# alte_schaltung.net
KiCad netlist of a schematic drawn in EAGLE
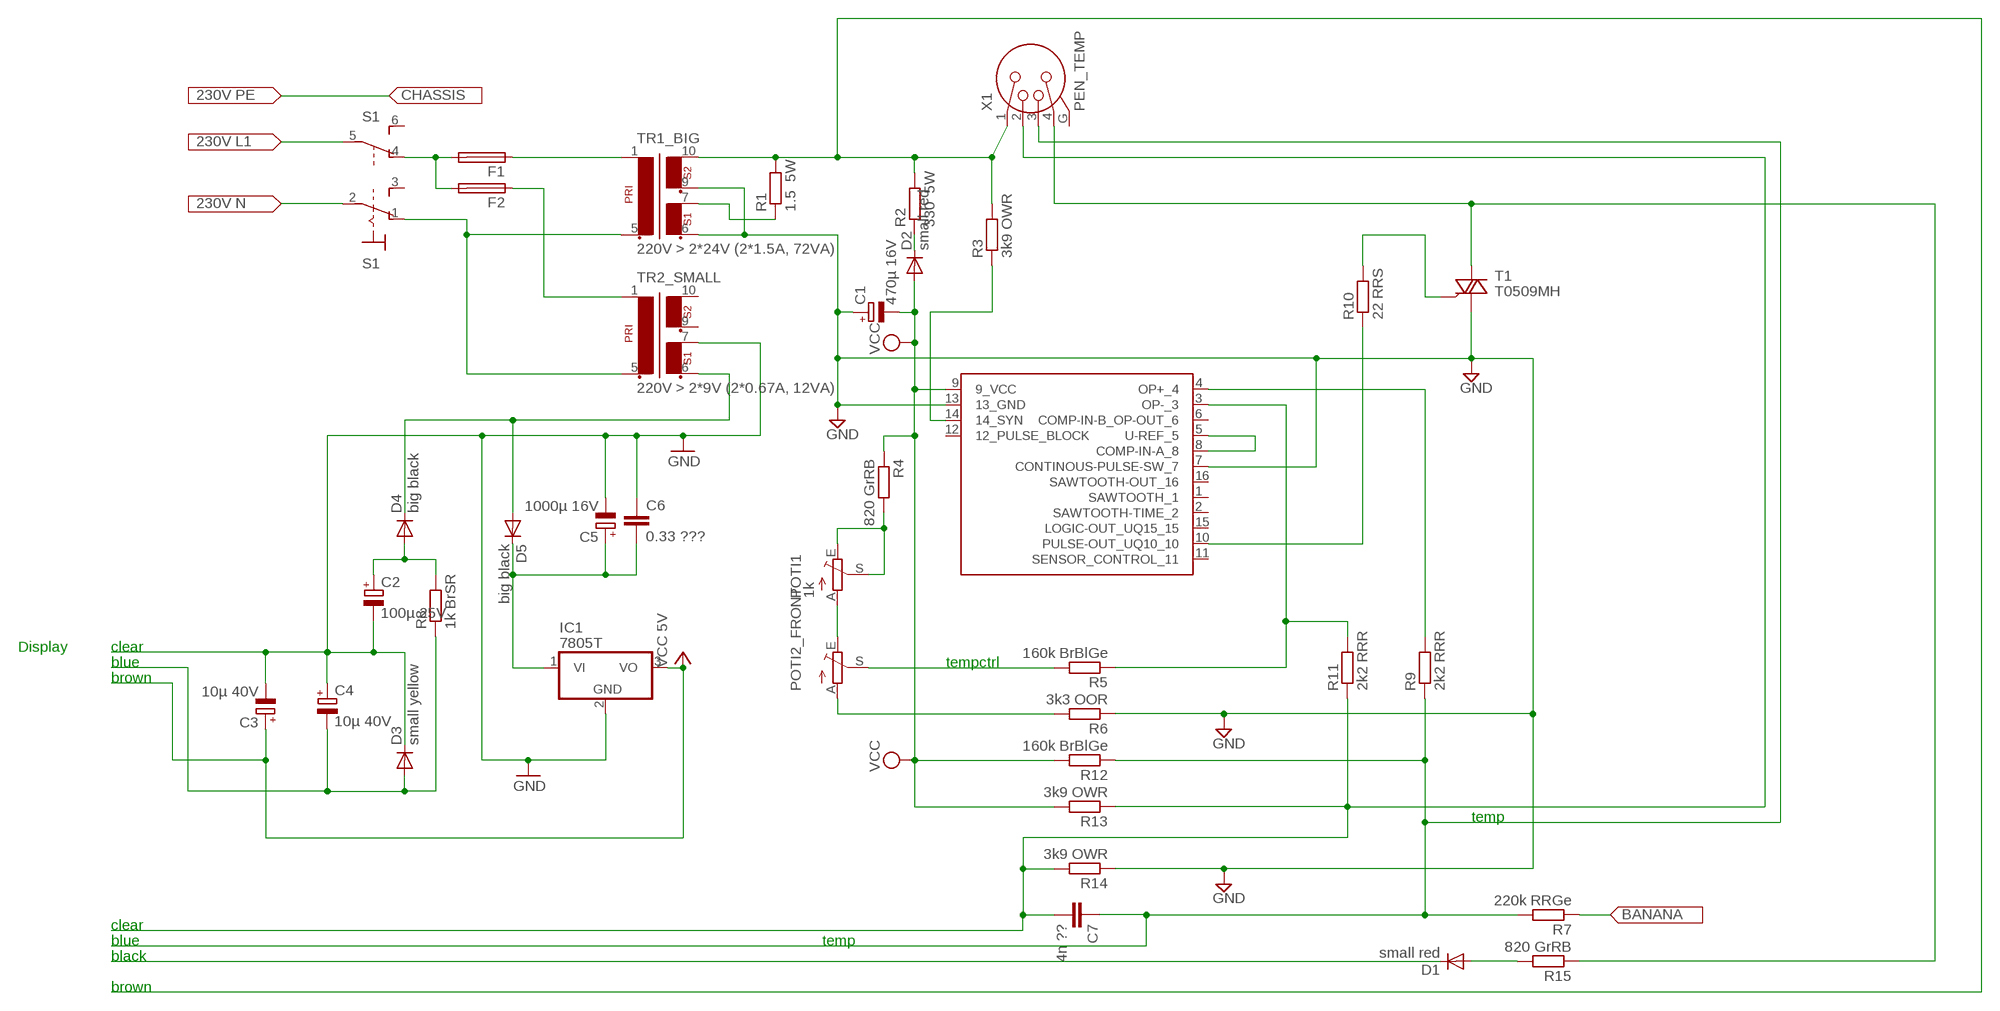
[diagram p0: schematic, sheet 1]

(export (version "E")
  (design (tool "Eeschema 10.0.6"))
  (components
    (comp (ref "C1")
      (value "470µ 16V")
      (footprint "eagle-import:E5-10,5")
      (libsource (lib "eagle-import") (part "CPOL-EUE5-10.5"))
    )
    (comp (ref "C2")
      (value "100µ 25V")
      (footprint "eagle-import:E5-10,5")
      (libsource (lib "eagle-import") (part "CPOL-EUE5-10.5"))
    )
    (comp (ref "C3")
      (value "10µ 40V")
      (footprint "eagle-import:E5-10,5")
      (libsource (lib "eagle-import") (part "CPOL-EUE5-10.5"))
    )
    (comp (ref "C4")
      (value "10µ 40V")
      (footprint "eagle-import:E5-10,5")
      (libsource (lib "eagle-import") (part "CPOL-EUE5-10.5"))
    )
    (comp (ref "C5")
      (value "1000µ 16V")
      (footprint "eagle-import:E5-10,5")
      (libsource (lib "eagle-import") (part "CPOL-EUE5-10.5"))
    )
    (comp (ref "C6")
      (value "0.33 ???")
      (footprint "eagle-import:C075-042X103")
      (libsource (lib "eagle-import") (part "C-EU075-042X103"))
    )
    (comp (ref "C7")
      (value "4n ??")
      (footprint "eagle-import:C050-024X044")
      (libsource (lib "eagle-import") (part "C-EU050-024X044"))
    )
    (comp (ref "D1")
      (value "small red")
      (footprint "eagle-import:DO41-10")
      (libsource (lib "eagle-import") (part "1N4004"))
    )
    (comp (ref "D2")
      (value "small red")
      (footprint "eagle-import:DO41-10")
      (libsource (lib "eagle-import") (part "1N4004"))
    )
    (comp (ref "D3")
      (value "small yellow")
      (footprint "eagle-import:DO35-10")
      (libsource (lib "eagle-import") (part "1N4446"))
    )
    (comp (ref "D4")
      (value "big black")
      (footprint "eagle-import:DO41-10")
      (libsource (lib "eagle-import") (part "1N4942"))
    )
    (comp (ref "D5")
      (value "big black")
      (footprint "eagle-import:DO41-10")
      (libsource (lib "eagle-import") (part "1N4942"))
    )
    (comp (ref "F1")
      (value "SH25")
      (footprint "eagle-import:SH25")
      (fields (field (name "MF") "SCHURTER") (field (name "MPN") "0031.8211"))
      (libsource (lib "eagle-import") (part "SH25"))
    )
    (comp (ref "F2")
      (value "SH25")
      (footprint "eagle-import:SH25")
      (fields (field (name "MF") "SCHURTER") (field (name "MPN") "0031.8211"))
      (libsource (lib "eagle-import") (part "SH25"))
    )
    (comp (ref "IC1")
      (value "7805T")
      (footprint "eagle-import:TO220H")
      (libsource (lib "eagle-import") (part "78T05"))
    )
    (comp (ref "POTI1")
      (value "1k")
      (footprint "eagle-import:LI10")
      (libsource (lib "eagle-import") (part "TRIM_EU-LI10"))
    )
    (comp (ref "POTI2_FRONT")
      (value "TRIM_EU-RJ9W")
      (footprint "eagle-import:RJ9W")
      (libsource (lib "eagle-import") (part "TRIM_EU-RJ9W"))
    )
    (comp (ref "R1")
      (value "1.5 5W")
      (footprint "eagle-import:0922_22")
      (libsource (lib "eagle-import") (part "R-EU_0922/22"))
    )
    (comp (ref "R2")
      (value "330 5W")
      (footprint "eagle-import:0922_22")
      (libsource (lib "eagle-import") (part "R-EU_0922/22"))
    )
    (comp (ref "R3")
      (value "3k9 OWR")
      (footprint "eagle-import:0207_12")
      (libsource (lib "eagle-import") (part "R-EU_0207/12"))
    )
    (comp (ref "R4")
      (value "820 GrRB")
      (footprint "eagle-import:0207_12")
      (libsource (lib "eagle-import") (part "R-EU_0207/12"))
    )
    (comp (ref "R5")
      (value "160k BrBlGe")
      (footprint "eagle-import:0207_12")
      (libsource (lib "eagle-import") (part "R-EU_0207/12"))
    )
    (comp (ref "R6")
      (value "3k3 OOR")
      (footprint "eagle-import:0207_12")
      (libsource (lib "eagle-import") (part "R-EU_0207/12"))
    )
    (comp (ref "R7")
      (value "220k RRGe")
      (footprint "eagle-import:0207_12")
      (libsource (lib "eagle-import") (part "R-EU_0207/12"))
    )
    (comp (ref "R8")
      (value "1k BrSR")
      (footprint "eagle-import:0207_12")
      (libsource (lib "eagle-import") (part "R-EU_0207/12"))
    )
    (comp (ref "R9")
      (value "2k2 RRR")
      (footprint "eagle-import:0207_12")
      (libsource (lib "eagle-import") (part "R-EU_0207/12"))
    )
    (comp (ref "R10")
      (value "22 RRS")
      (footprint "eagle-import:0207_12")
      (libsource (lib "eagle-import") (part "R-EU_0207/12"))
    )
    (comp (ref "R11")
      (value "2k2 RRR")
      (footprint "eagle-import:0207_12")
      (libsource (lib "eagle-import") (part "R-EU_0207/12"))
    )
    (comp (ref "R12")
      (value "160k BrBlGe")
      (footprint "eagle-import:0207_12")
      (libsource (lib "eagle-import") (part "R-EU_0207/12"))
    )
    (comp (ref "R13")
      (value "3k9 OWR")
      (footprint "eagle-import:0207_12")
      (libsource (lib "eagle-import") (part "R-EU_0207/12"))
    )
    (comp (ref "R14")
      (value "3k9 OWR")
      (footprint "eagle-import:0207_12")
      (libsource (lib "eagle-import") (part "R-EU_0207/12"))
    )
    (comp (ref "R15")
      (value "820 GrRB")
      (footprint "eagle-import:0207_12")
      (libsource (lib "eagle-import") (part "R-EU_0207/12"))
    )
    (comp (ref "S1")
      (value "320-938")
      (footprint "eagle-import:320-938")
      (libsource (lib "eagle-import") (part "320-938"))
    )
    (comp (ref "T1")
      (value "T0509MH")
      (footprint "eagle-import:TO220AB")
      (libsource (lib "eagle-import") (part "BT136"))
    )
    (comp (ref "TR1_BIG")
      (value "220V > 2*24V (2*1.5A, 72VA)")
      (footprint "eagle-import:EI42-2")
      (libsource (lib "eagle-import") (part "EI42-2"))
    )
    (comp (ref "TR2_SMALL")
      (value "220V > 2*9V (2*0.67A, 12VA)")
      (footprint "eagle-import:EI42-2")
      (libsource (lib "eagle-import") (part "EI42-2"))
    )
    (comp (ref "U$1")
      (value "U106BS-DIL16")
      (footprint "eagle-import:DIL16")
      (libsource (lib "eagle-import") (part "U106BS-DIL16"))
    )
    (comp (ref "X1")
      (value "PEN_TEMP")
      (footprint "eagle-import:NC4FBV")
      (fields (field (name "MPN") "NC4FBV"))
      (libsource (lib "eagle-import") (part "NC4FBV"))
    )
  )
  (nets
    (net (code "1") (name "GND") (class "Default")
      (node (ref "C1") (pin "+") (pinfunction "+_+") (pintype "passive"))
      (node (ref "C2") (pin "-") (pinfunction "-_-") (pintype "passive"))
      (node (ref "C3") (pin "-") (pinfunction "-_-") (pintype "passive"))
      (node (ref "C4") (pin "+") (pinfunction "+_+") (pintype "passive"))
      (node (ref "C5") (pin "-") (pinfunction "-_-") (pintype "passive"))
      (node (ref "C6") (pin "1") (pinfunction "1_1") (pintype "passive"))
      (node (ref "D3") (pin "C") (pinfunction "C_C") (pintype "passive"))
      (node (ref "IC1") (pin "2") (pinfunction "GND_2") (pintype "passive"))
      (node (ref "R14") (pin "1") (pinfunction "1_1") (pintype "passive"))
      (node (ref "R6") (pin "1") (pinfunction "1_1") (pintype "passive"))
      (node (ref "T1") (pin "1") (pinfunction "A1_1") (pintype "passive"))
      (node (ref "TR1_BIG") (pin "6") (pinfunction "3_6") (pintype "passive"))
      (node (ref "TR1_BIG") (pin "9") (pinfunction "5_9") (pintype "passive"))
      (node (ref "TR2_SMALL") (pin "7") (pinfunction "4_7") (pintype "passive"))
      (node (ref "U$1") (pin "13") (pinfunction "13_GND_13") (pintype "power_in"))
      (node (ref "U$1") (pin "7") (pinfunction "CONTINOUS-PULSE-SW_7_7") (pintype "input"))
    )
    (net (code "2") (name "Net-(C2-Pad+)") (class "Default")
      (node (ref "C2") (pin "+") (pinfunction "+_+") (pintype "passive"))
      (node (ref "D4") (pin "A") (pinfunction "A_A") (pintype "passive"))
      (node (ref "R8") (pin "2") (pinfunction "2_2") (pintype "passive"))
    )
    (net (code "3") (name "Net-(C4-Pad-)") (class "Default")
      (node (ref "C4") (pin "-") (pinfunction "-_-") (pintype "passive"))
      (node (ref "D3") (pin "A") (pinfunction "A_A") (pintype "passive"))
      (node (ref "R8") (pin "1") (pinfunction "1_1") (pintype "passive"))
    )
    (net (code "4") (name "Net-(C7-Pad1)") (class "Default")
      (node (ref "C7") (pin "1") (pinfunction "1_1") (pintype "passive"))
      (node (ref "R12") (pin "1") (pinfunction "1_1") (pintype "passive"))
      (node (ref "R7") (pin "2") (pinfunction "2_2") (pintype "passive"))
      (node (ref "R9") (pin "1") (pinfunction "1_1") (pintype "passive"))
      (node (ref "X1") (pin "3") (pinfunction "3_3") (pintype "passive"))
    )
    (net (code "5") (name "Net-(C7-Pad2)") (class "Default")
      (node (ref "C7") (pin "2") (pinfunction "2_2") (pintype "passive"))
      (node (ref "R11") (pin "1") (pinfunction "1_1") (pintype "passive"))
      (node (ref "R13") (pin "1") (pinfunction "1_1") (pintype "passive"))
      (node (ref "R14") (pin "2") (pinfunction "2_2") (pintype "passive"))
      (node (ref "X1") (pin "2") (pinfunction "2_2") (pintype "passive"))
    )
    (net (code "6") (name "Net-(D1-PadA)") (class "Default")
      (node (ref "D1") (pin "A") (pinfunction "A_A") (pintype "passive"))
      (node (ref "R15") (pin "2") (pinfunction "2_2") (pintype "passive"))
    )
    (net (code "7") (name "Net-(D2-PadC)") (class "Default")
      (node (ref "D2") (pin "C") (pinfunction "C_C") (pintype "passive"))
      (node (ref "R2") (pin "1") (pinfunction "1_1") (pintype "passive"))
    )
    (net (code "8") (name "Net-(F1-Pad1)") (class "Default")
      (node (ref "F1") (pin "1") (pinfunction "1_1") (pintype "passive"))
      (node (ref "TR1_BIG") (pin "1") (pinfunction "1_1") (pintype "passive"))
    )
    (net (code "9") (name "Net-(F2-Pad1)") (class "Default")
      (node (ref "F2") (pin "1") (pinfunction "1_1") (pintype "passive"))
      (node (ref "TR2_SMALL") (pin "1") (pinfunction "1_1") (pintype "passive"))
    )
    (net (code "10") (name "Net-(IC1-VI)") (class "Default")
      (node (ref "C5") (pin "+") (pinfunction "+_+") (pintype "passive"))
      (node (ref "C6") (pin "2") (pinfunction "2_2") (pintype "passive"))
      (node (ref "D5") (pin "C") (pinfunction "C_C") (pintype "passive"))
      (node (ref "IC1") (pin "1") (pinfunction "VI_1") (pintype "input"))
    )
    (net (code "11") (name "Net-(POTI1-PadA)") (class "Default")
      (node (ref "POTI1") (pin "A") (pinfunction "A_A") (pintype "passive"))
      (node (ref "POTI2_FRONT") (pin "E") (pinfunction "E_E") (pintype "passive"))
    )
    (net (code "12") (name "Net-(POTI1-PadE)") (class "Default")
      (node (ref "POTI1") (pin "E") (pinfunction "E_E") (pintype "passive"))
      (node (ref "POTI1") (pin "S") (pinfunction "S_S") (pintype "passive"))
      (node (ref "R4") (pin "2") (pinfunction "2_2") (pintype "passive"))
    )
    (net (code "13") (name "Net-(POTI2_FRONT-PadA)") (class "Default")
      (node (ref "POTI2_FRONT") (pin "A") (pinfunction "A_A") (pintype "passive"))
      (node (ref "R6") (pin "2") (pinfunction "2_2") (pintype "passive"))
    )
    (net (code "14") (name "Net-(POTI2_FRONT-PadS)") (class "Default")
      (node (ref "POTI2_FRONT") (pin "S") (pinfunction "S_S") (pintype "passive"))
      (node (ref "R5") (pin "2") (pinfunction "2_2") (pintype "passive"))
    )
    (net (code "15") (name "Net-(S1A-O)") (class "Default")
      (node (ref "S1") (pin "1") (pinfunction "O_1") (pintype "passive"))
      (node (ref "TR1_BIG") (pin "5") (pinfunction "2_5") (pintype "passive"))
      (node (ref "TR2_SMALL") (pin "5") (pinfunction "2_5") (pintype "passive"))
    )
    (net (code "16") (name "Net-(S1B-O)") (class "Default")
      (node (ref "F1") (pin "2") (pinfunction "2_2") (pintype "passive"))
      (node (ref "F2") (pin "2") (pinfunction "2_2") (pintype "passive"))
      (node (ref "S1") (pin "4") (pinfunction "O_4") (pintype "passive"))
    )
    (net (code "17") (name "Net-(T1-A2)") (class "Default")
      (node (ref "R15") (pin "1") (pinfunction "1_1") (pintype "passive"))
      (node (ref "T1") (pin "2") (pinfunction "A2_2") (pintype "passive"))
      (node (ref "X1") (pin "4") (pinfunction "4_4") (pintype "passive"))
    )
    (net (code "18") (name "Net-(T1-G)") (class "Default")
      (node (ref "R10") (pin "2") (pinfunction "2_2") (pintype "passive"))
      (node (ref "T1") (pin "3") (pinfunction "G_3") (pintype "passive"))
    )
    (net (code "19") (name "Net-(TR1_BIG-4)") (class "Default")
      (node (ref "R1") (pin "1") (pinfunction "1_1") (pintype "passive"))
      (node (ref "TR1_BIG") (pin "7") (pinfunction "4_7") (pintype "passive"))
    )
    (net (code "20") (name "Net-(TR1_BIG-6)") (class "Default")
      (node (ref "R1") (pin "2") (pinfunction "2_2") (pintype "passive"))
      (node (ref "R2") (pin "2") (pinfunction "2_2") (pintype "passive"))
      (node (ref "R3") (pin "2") (pinfunction "2_2") (pintype "passive"))
      (node (ref "TR1_BIG") (pin "10") (pinfunction "6_10") (pintype "passive"))
      (node (ref "X1") (pin "1") (pinfunction "1_1") (pintype "passive"))
    )
    (net (code "21") (name "Net-(TR2_SMALL-3)") (class "Default")
      (node (ref "D4") (pin "C") (pinfunction "C_C") (pintype "passive"))
      (node (ref "D5") (pin "A") (pinfunction "A_A") (pintype "passive"))
      (node (ref "TR2_SMALL") (pin "6") (pinfunction "3_6") (pintype "passive"))
    )
    (net (code "22") (name "Net-(U$1-14_SYN)") (class "Default")
      (node (ref "R3") (pin "1") (pinfunction "1_1") (pintype "passive"))
      (node (ref "U$1") (pin "14") (pinfunction "14_SYN_14") (pintype "input"))
    )
    (net (code "23") (name "Net-(U$1-COMP-IN-A_8)") (class "Default")
      (node (ref "U$1") (pin "5") (pinfunction "U-REF_5_5") (pintype "input"))
      (node (ref "U$1") (pin "8") (pinfunction "COMP-IN-A_8_8") (pintype "input"))
    )
    (net (code "24") (name "Net-(U$1-OP+_4)") (class "Default")
      (node (ref "R9") (pin "2") (pinfunction "2_2") (pintype "passive"))
      (node (ref "U$1") (pin "4") (pinfunction "OP+_4_4") (pintype "input"))
    )
    (net (code "25") (name "Net-(U$1-OP-_3)") (class "Default")
      (node (ref "R11") (pin "2") (pinfunction "2_2") (pintype "passive"))
      (node (ref "R5") (pin "1") (pinfunction "1_1") (pintype "passive"))
      (node (ref "U$1") (pin "3") (pinfunction "OP-_3_3") (pintype "input"))
    )
    (net (code "26") (name "Net-(U$1-PULSE-OUT_UQ10_10)") (class "Default")
      (node (ref "R10") (pin "1") (pinfunction "1_1") (pintype "passive"))
      (node (ref "U$1") (pin "10") (pinfunction "PULSE-OUT_UQ10_10_10") (pintype "output"))
    )
    (net (code "27") (name "VCC") (class "Default")
      (node (ref "C1") (pin "-") (pinfunction "-_-") (pintype "passive"))
      (node (ref "C3") (pin "+") (pinfunction "+_+") (pintype "passive"))
      (node (ref "D2") (pin "A") (pinfunction "A_A") (pintype "passive"))
      (node (ref "IC1") (pin "3") (pinfunction "VO_3") (pintype "passive"))
      (node (ref "R12") (pin "2") (pinfunction "2_2") (pintype "passive"))
      (node (ref "R13") (pin "2") (pinfunction "2_2") (pintype "passive"))
      (node (ref "R4") (pin "1") (pinfunction "1_1") (pintype "passive"))
      (node (ref "U$1") (pin "9") (pinfunction "9_VCC_9") (pintype "power_in"))
    )
    (net (code "28") (name "unconnected-(D1-PadC)") (class "Default")
      (node (ref "D1") (pin "C") (pinfunction "C_C") (pintype "passive"))
    )
    (net (code "29") (name "unconnected-(R7-Pad1)") (class "Default")
      (node (ref "R7") (pin "1") (pinfunction "1_1") (pintype "passive"))
    )
    (net (code "30") (name "unconnected-(S1A-P-Pad2)") (class "Default")
      (node (ref "S1") (pin "2") (pinfunction "P_2") (pintype "passive"))
    )
    (net (code "31") (name "unconnected-(S1A-S-Pad3)") (class "Default")
      (node (ref "S1") (pin "3") (pinfunction "S_3") (pintype "passive"))
    )
    (net (code "32") (name "unconnected-(S1B-P-Pad5)") (class "Default")
      (node (ref "S1") (pin "5") (pinfunction "P_5") (pintype "passive"))
    )
    (net (code "33") (name "unconnected-(S1B-S-Pad6)") (class "Default")
      (node (ref "S1") (pin "6") (pinfunction "S_6") (pintype "passive"))
    )
    (net (code "34") (name "unconnected-(TR2_SMALL-5-Pad9)") (class "Default")
      (node (ref "TR2_SMALL") (pin "9") (pinfunction "5_9") (pintype "passive"))
    )
    (net (code "35") (name "unconnected-(TR2_SMALL-6-Pad10)") (class "Default")
      (node (ref "TR2_SMALL") (pin "10") (pinfunction "6_10") (pintype "passive"))
    )
    (net (code "36") (name "unconnected-(U$1-12_PULSE_BLOCK-Pad12)") (class "Default")
      (node (ref "U$1") (pin "12") (pinfunction "12_PULSE_BLOCK_12") (pintype "input"))
    )
    (net (code "37") (name "unconnected-(U$1-COMP-IN-B_OP-OUT_6-Pad6)") (class "Default")
      (node (ref "U$1") (pin "6") (pinfunction "COMP-IN-B_OP-OUT_6_6") (pintype "output"))
    )
    (net (code "38") (name "unconnected-(U$1-LOGIC-OUT_UQ15_15-Pad15)") (class "Default")
      (node (ref "U$1") (pin "15") (pinfunction "LOGIC-OUT_UQ15_15_15") (pintype "output"))
    )
    (net (code "39") (name "unconnected-(U$1-SAWTOOTH-OUT_16-Pad16)") (class "Default")
      (node (ref "U$1") (pin "16") (pinfunction "SAWTOOTH-OUT_16_16") (pintype "output"))
    )
    (net (code "40") (name "unconnected-(U$1-SAWTOOTH-TIME_2-Pad2)") (class "Default")
      (node (ref "U$1") (pin "2") (pinfunction "SAWTOOTH-TIME_2_2") (pintype "input"))
    )
    (net (code "41") (name "unconnected-(U$1-SAWTOOTH_1-Pad1)") (class "Default")
      (node (ref "U$1") (pin "1") (pinfunction "SAWTOOTH_1_1") (pintype "input"))
    )
    (net (code "42") (name "unconnected-(U$1-SENSOR_CONTROL_11-Pad11)") (class "Default")
      (node (ref "U$1") (pin "11") (pinfunction "SENSOR_CONTROL_11_11") (pintype "input"))
    )
    (net (code "43") (name "unconnected-(X1-PadG)") (class "Default")
      (node (ref "X1") (pin "G") (pinfunction "G_G") (pintype "passive"))
    )
  )
)
